# Sheet_cv.net
KiCad netlist of a schematic drawn in Altium Designer
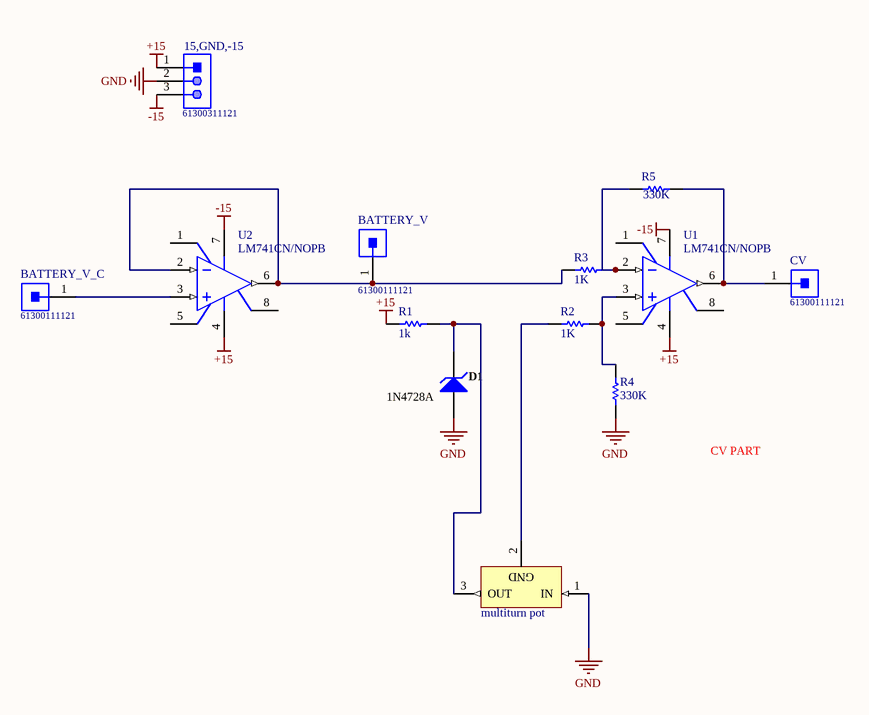
[diagram p0: Sheet_cv.SchDoc]

(export (version "E")
  (design (tool "Eeschema 10.0.6"))
  (components
    (comp (ref "15,GND,-15")
      (value "61300311121")
      (footprint "61300311121")
      (description "THT Vertical Pin Header WR-PHD, Pitch 2.54 mm, Single Row, 3 pins")
      (fields (field (name "MANUFACTURER") "Wurth Elektronik") (field (name "PUBLISHER") "WurthElektronik"))
      (libsource (lib "Altium Content Vault") (part "WE-CN-1P-M-R3"))
    )
    (comp (ref "BATTERY_V")
      (value "61300111121")
      (footprint "61300111121")
      (description "THT Vertical Pin Header WR-PHD, Pitch 2.54 mm, Single Row, 1 pins")
      (fields (field (name "MANUFACTURER") "Wurth Elektronik") (field (name "PUBLISHER") "WurthElektronik"))
      (libsource (lib "") (part "WE-CN-1P-M-R1_2"))
    )
    (comp (ref "BATTERY_V_C")
      (value "61300111121")
      (footprint "61300111121")
      (description "THT Vertical Pin Header WR-PHD, Pitch 2.54 mm, Single Row, 1 pins")
      (fields (field (name "MANUFACTURER") "Wurth Elektronik") (field (name "PUBLISHER") "WurthElektronik"))
      (libsource (lib "Altium Content Vault") (part "WE-CN-1P-M-R1"))
    )
    (comp (ref "CV")
      (value "61300111121")
      (footprint "61300111121")
      (description "THT Vertical Pin Header WR-PHD, Pitch 2.54 mm, Single Row, 1 pins")
      (fields (field (name "MANUFACTURER") "Wurth Elektronik") (field (name "PUBLISHER") "WurthElektronik"))
      (libsource (lib "") (part "WE-CN-1P-M-R1_1"))
    )
    (comp (ref "D1")
      (value "1N4728A")
      (footprint "FAIR-DO-41-2_V")
      (description "Zener Diode, 3.3V, 1W, 5%, -65 to 200 degC, 2-Pin DO-41, Body 2.72 x 5.2 mm, RoHS")
      (fields (field (name "MANUFACTURER") "Fairchild Semiconductor") (field (name "TOLERANCE") "5%"))
      (libsource (lib "Altium Content Vault") (part "FAIR-DZEN-A1K2-2"))
    )
    (comp (ref "multiturn pot")
      (value "~")
      (footprint "FAIR-TO-220-3")
      (description "Positive Voltage Regulator, 5 V, 1 A, -40 to 125 degC, 3-Pin TO-220, RoHS, Tube")
      (fields (field (name "MANUFACTURER") "FairchildSemiconductor"))
      (libsource (lib "Altium Content Vault") (part "FAIR-LM7805CT-TO220-3"))
    )
    (comp (ref "R1")
      (value "1k")
      (footprint "RESA60-630X240")
      (description "Axial Resistor, 1 KOhm, +/- 1%, 250 mW, -55 to 155 degC, 2-Pin THD, RoHS, Bulk")
      (fields (field (name "TOLERANCE") "1%"))
      (libsource (lib "Altium Content Vault") (part "RES-2"))
    )
    (comp (ref "R2")
      (value "1K")
      (footprint "RESA60-630X240")
      (description "Axial Resistor, 1 KOhm, +/- 1%, 250 mW, -55 to 155 degC, 2-Pin THD, RoHS, Bulk")
      (fields (field (name "TOLERANCE") "1%"))
      (libsource (lib "Altium Content Vault") (part "RES-2"))
    )
    (comp (ref "R3")
      (value "1K")
      (footprint "RESA60-630X240")
      (description "Axial Resistor, 1 KOhm, +/- 1%, 250 mW, -55 to 155 degC, 2-Pin THD, RoHS, Bulk")
      (fields (field (name "TOLERANCE") "1%"))
      (libsource (lib "Altium Content Vault") (part "RES-2"))
    )
    (comp (ref "R4")
      (value "330K")
      (footprint "RESA60-630X240")
      (description "Axial Resistor, 1 KOhm, +/- 1%, 250 mW, -55 to 155 degC, 2-Pin THD, RoHS, Bulk")
      (fields (field (name "TOLERANCE") "1%"))
      (libsource (lib "Altium Content Vault") (part "RES-2"))
    )
    (comp (ref "R5")
      (value "330K")
      (footprint "RESA60-630X240")
      (description "Axial Resistor, 1 KOhm, +/- 1%, 250 mW, -55 to 155 degC, 2-Pin THD, RoHS, Bulk")
      (fields (field (name "TOLERANCE") "1%"))
      (libsource (lib "Altium Content Vault") (part "RES-2"))
    )
    (comp (ref "U1")
      (value "LM741CN/NOPB")
      (footprint "P0008A")
      (description "Operational Amplifier, 8-pin MDIP, Pb-Free")
      (fields (field (name "MANUFACTURER") "Texas Instruments"))
      (libsource (lib "Altium Content Vault") (part "AMP-OPA-LM741-8"))
    )
    (comp (ref "U2")
      (value "LM741CN/NOPB")
      (footprint "P0008A")
      (description "Operational Amplifier, 8-pin MDIP, Pb-Free")
      (fields (field (name "MANUFACTURER") "Texas Instruments"))
      (libsource (lib "Altium Content Vault") (part "AMP-OPA-LM741-8"))
    )
  )
  (nets
    (net (code "1") (name "+15") (class "Default")
      (node (ref "15,GND,-15") (pin "1") (pinfunction "1_1") (pintype "passive"))
      (node (ref "R1") (pin "1") (pinfunction "1_1") (pintype "passive"))
      (node (ref "U1") (pin "4") (pinfunction "V-_4") (pintype "power_in"))
      (node (ref "U2") (pin "4") (pinfunction "V-_4") (pintype "power_in"))
    )
    (net (code "2") (name "-15") (class "Default")
      (node (ref "15,GND,-15") (pin "3") (pinfunction "3_3") (pintype "passive"))
      (node (ref "U1") (pin "7") (pinfunction "V+_7") (pintype "power_in"))
      (node (ref "U2") (pin "7") (pinfunction "V+_7") (pintype "power_in"))
    )
    (net (code "3") (name "GND") (class "Default")
      (node (ref "15,GND,-15") (pin "2") (pinfunction "2_2") (pintype "passive"))
      (node (ref "D1") (pin "1") (pinfunction "A_1") (pintype "passive"))
      (node (ref "R4") (pin "1") (pinfunction "1_1") (pintype "passive"))
      (node (ref "multiturn pot") (pin "1") (pinfunction "IN_1") (pintype "input"))
    )
    (net (code "4") (name "Net-(D1-K)") (class "Default")
      (node (ref "D1") (pin "2") (pinfunction "K_2") (pintype "passive"))
      (node (ref "R1") (pin "2") (pinfunction "2_2") (pintype "passive"))
      (node (ref "multiturn pot") (pin "3") (pinfunction "OUT_3") (pintype "output"))
    )
    (net (code "5") (name "Net-(U1-IN+)") (class "Default")
      (node (ref "R2") (pin "2") (pinfunction "2_2") (pintype "passive"))
      (node (ref "R4") (pin "2") (pinfunction "2_2") (pintype "passive"))
      (node (ref "U1") (pin "3") (pinfunction "IN+_3") (pintype "input"))
    )
    (net (code "6") (name "Net-(U1-IN-)") (class "Default")
      (node (ref "R3") (pin "1") (pinfunction "1_1") (pintype "passive"))
      (node (ref "R5") (pin "2") (pinfunction "2_2") (pintype "passive"))
      (node (ref "U1") (pin "2") (pinfunction "IN-_2") (pintype "input"))
    )
    (net (code "7") (name "Net-(U1-OUT)") (class "Default")
      (node (ref "CV") (pin "1") (pinfunction "1_1") (pintype "passive"))
      (node (ref "R5") (pin "1") (pinfunction "1_1") (pintype "passive"))
      (node (ref "U1") (pin "6") (pinfunction "OUT_6") (pintype "output"))
    )
    (net (code "8") (name "Net-(U2-IN+)") (class "Default")
      (node (ref "BATTERY_V_C") (pin "1") (pinfunction "1_1") (pintype "passive"))
      (node (ref "U2") (pin "3") (pinfunction "IN+_3") (pintype "input"))
    )
    (net (code "9") (name "Net-(U2-IN-)") (class "Default")
      (node (ref "BATTERY_V") (pin "1") (pinfunction "1_1") (pintype "passive"))
      (node (ref "R3") (pin "2") (pinfunction "2_2") (pintype "passive"))
      (node (ref "U2") (pin "2") (pinfunction "IN-_2") (pintype "input"))
      (node (ref "U2") (pin "6") (pinfunction "OUT_6") (pintype "output"))
    )
    (net (code "10") (name "Net-(multiturn pot-GND)") (class "Default")
      (node (ref "R2") (pin "1") (pinfunction "1_1") (pintype "passive"))
      (node (ref "multiturn pot") (pin "2") (pinfunction "GND_2") (pintype "power_in"))
    )
    (net (code "11") (name "unconnected-(U1-NC-Pad8)") (class "Default")
      (node (ref "U1") (pin "8") (pinfunction "NC_8") (pintype "passive"))
    )
    (net (code "12") (name "unconnected-(U1-OFS_NULL-Pad1)") (class "Default")
      (node (ref "U1") (pin "1") (pinfunction "OFS_NULL_1") (pintype "passive"))
    )
    (net (code "13") (name "unconnected-(U1-OFS_NULL-Pad5)") (class "Default")
      (node (ref "U1") (pin "5") (pinfunction "OFS_NULL_5") (pintype "passive"))
    )
    (net (code "14") (name "unconnected-(U2-NC-Pad8)") (class "Default")
      (node (ref "U2") (pin "8") (pinfunction "NC_8") (pintype "passive"))
    )
    (net (code "15") (name "unconnected-(U2-OFS_NULL-Pad1)") (class "Default")
      (node (ref "U2") (pin "1") (pinfunction "OFS_NULL_1") (pintype "passive"))
    )
    (net (code "16") (name "unconnected-(U2-OFS_NULL-Pad5)") (class "Default")
      (node (ref "U2") (pin "5") (pinfunction "OFS_NULL_5") (pintype "passive"))
    )
  )
)
